# Power.net
KiCad netlist of a schematic drawn in Altium Designer
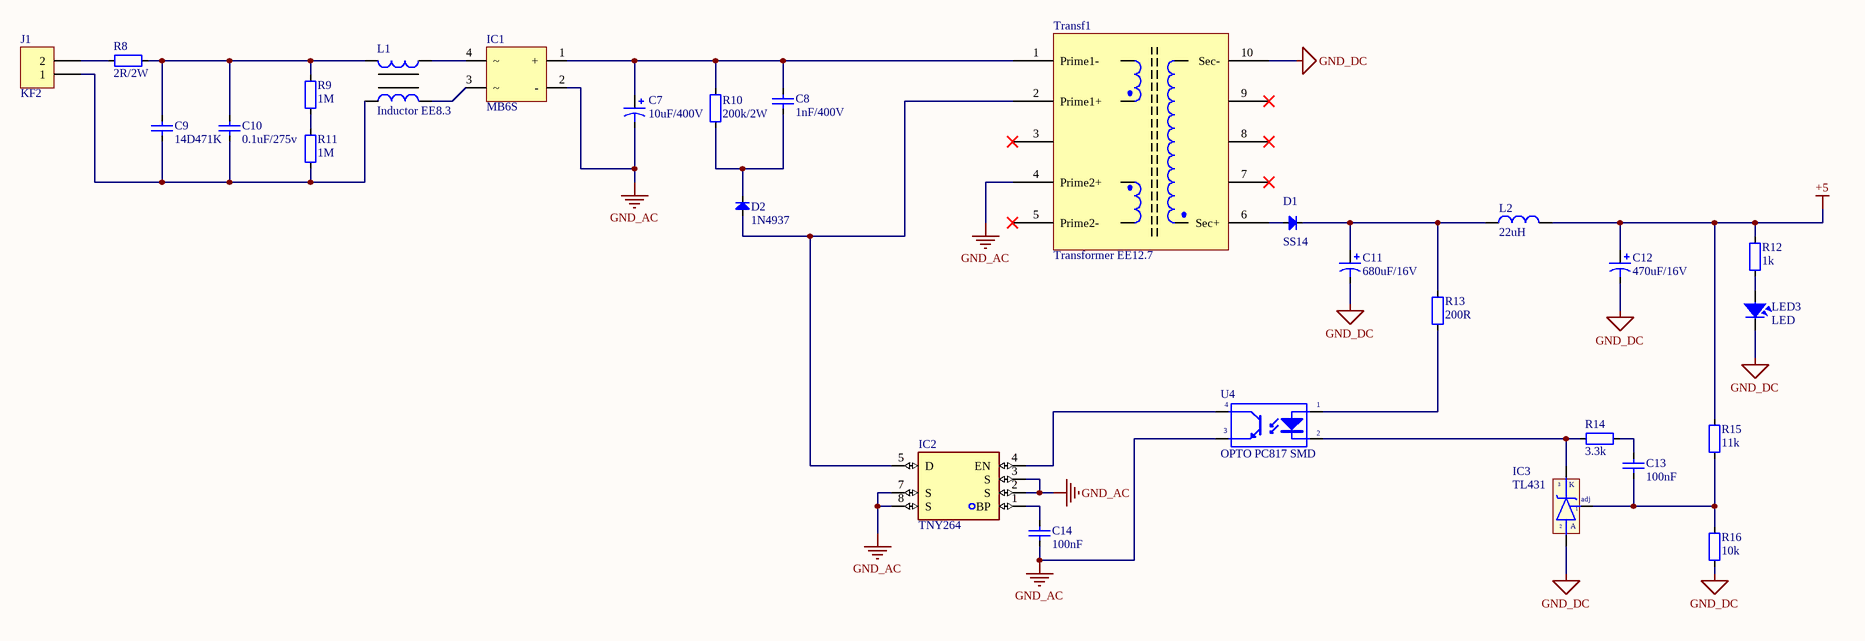
[diagram p0: Power.SchDoc]

(export (version "E")
  (design (tool "Eeschema 10.0.6"))
  (components
    (comp (ref "C7")
      (value "10uF/400V")
      (footprint "C10mm")
      (description "Polarized Capacitor (Axial)")
      (fields (field (name "PUBLISHER") "Altium Limited"))
      (libsource (lib "My Library") (part "Cap Pol"))
    )
    (comp (ref "C8")
      (value "1nF/400V")
      (footprint "103/2KV")
      (description "CAP CERAMIC")
      (fields (field (name "PUBLISHER") "Altium Limited"))
      (libsource (lib "My Library") (part "Cap2KV"))
    )
    (comp (ref "C9")
      (value "14D471K")
      (footprint "103/2KV")
      (description "Capacitor Ceramic 2KV")
      (fields (field (name "PUBLISHER") "Altium Limited"))
      (libsource (lib "My Library") (part "Cap2KV"))
    )
    (comp (ref "C10")
      (value "0.1uF/275v")
      (footprint "Cap AC filter")
      (description "Tụ lọc nguồn AC 0.1uf 275v 10mm")
      (libsource (lib "My Library") (part "Cap AC filter"))
    )
    (comp (ref "C11")
      (value "680uF/16V")
      (footprint "C8mm")
      (description "Polarized Capacitor (Axial)")
      (fields (field (name "PUBLISHER") "Altium Limited"))
      (libsource (lib "My Library") (part "Cap Pol"))
    )
    (comp (ref "C12")
      (value "470uF/16V")
      (footprint "C8mm")
      (description "Polarized Capacitor (Axial)")
      (fields (field (name "PUBLISHER") "Altium Limited"))
      (libsource (lib "My Library") (part "Cap Pol"))
    )
    (comp (ref "C13")
      (value "100nF")
      (footprint "CAP_0805")
      (description "Capacitor")
      (fields (field (name "PUBLISHER") "Altium Limited"))
      (libsource (lib "My Library") (part "CapSMD"))
    )
    (comp (ref "C14")
      (value "100nF")
      (footprint "CAP_0805")
      (description "Capacitor")
      (fields (field (name "PUBLISHER") "Altium Limited"))
      (libsource (lib "My Library") (part "CapSMD"))
    )
    (comp (ref "D1")
      (value "SS14")
      (footprint "DO-214AC(SMA)")
      (description "Diode Schottky\r\n1N5819")
      (fields (field (name "PUBLISHER") "Altium Limited"))
      (libsource (lib "My Library") (part "Diode SMD"))
    )
    (comp (ref "D2")
      (value "1N4937")
      (footprint "DIO-1AN")
      (description "Diode Schottky\r\n1N4937")
      (fields (field (name "PUBLISHER") "Altium Limited"))
      (libsource (lib "My Library") (part "Diode SMD"))
    )
    (comp (ref "IC1") (value "MB6S") (footprint "MB6S") (libsource (lib "My Library") (part "MB6S")))
    (comp (ref "IC2")
      (value "TNY264")
      (footprint "TNY264")
      (description "IC Power")
      (libsource (lib "My Library") (part "TNY264"))
    )
    (comp (ref "IC3")
      (value "TL431")
      (footprint "qto-92")
      (description "Programmable Shunt Regulator")
      (libsource (lib "My Library") (part "TL431"))
    )
    (comp (ref "J1")
      (value "KF2")
      (footprint "KF2-5.08T")
      (fields
        (field (name "MANUFACTURER") "Würth Elektronik eiSos GmbH")
        (field (name "PARTNO") "691103110002")
        (field (name "CREATED BY") "Karrer Zheng")
      )
      (libsource (lib "My Library") (part "KF2"))
    )
    (comp (ref "L1")
      (value "Inductor EE8.3")
      (footprint "Inductor EE8.3")
      (libsource (lib "My Library") (part "Inductor EE8.3"))
    )
    (comp (ref "L2")
      (value "22uH")
      (footprint "L_SMD")
      (description "CD73R 22uH 1.23A 7345")
      (libsource (lib "My Library") (part "Inductor"))
    )
    (comp (ref "LED3")
      (value "LED")
      (footprint "LED-0805-Red")
      (description "LED Single colour Green and Red")
      (libsource (lib "My Library") (part "LED"))
    )
    (comp (ref "R8")
      (value "2R/2W")
      (footprint "RES-1WW")
      (description "Resistor")
      (fields
        (field (name "MANUFACTURER") "Generic Components")
        (field (name "PUBLISHER") "Altium Hobart Technology Centre")
      )
      (libsource (lib "My Library") (part "Resistor - SMD"))
    )
    (comp (ref "R9")
      (value "1M")
      (footprint "RES-SMD-1206")
      (description "Resistor")
      (fields
        (field (name "MANUFACTURER") "Generic Components")
        (field (name "PUBLISHER") "Altium Hobart Technology Centre")
      )
      (libsource (lib "My Library") (part "Resistor - SMD"))
    )
    (comp (ref "R10")
      (value "200k/2W")
      (footprint "RES-1WW")
      (description "Resistor")
      (fields
        (field (name "MANUFACTURER") "Generic Components")
        (field (name "PUBLISHER") "Altium Hobart Technology Centre")
      )
      (libsource (lib "My Library") (part "Resistor - SMD"))
    )
    (comp (ref "R11")
      (value "1M")
      (footprint "RES-SMD-1206")
      (description "Resistor")
      (fields
        (field (name "MANUFACTURER") "Generic Components")
        (field (name "PUBLISHER") "Altium Hobart Technology Centre")
      )
      (libsource (lib "My Library") (part "Resistor - SMD"))
    )
    (comp (ref "R12")
      (value "1k")
      (footprint "RES-SMD-0805")
      (description "Resistor")
      (fields
        (field (name "MANUFACTURER") "Generic Components")
        (field (name "PUBLISHER") "Altium Hobart Technology Centre")
      )
      (libsource (lib "My Library") (part "Resistor - SMD"))
    )
    (comp (ref "R13")
      (value "200R")
      (footprint "RES-SMD-0805")
      (description "Resistor")
      (fields
        (field (name "MANUFACTURER") "Generic Components")
        (field (name "PUBLISHER") "Altium Hobart Technology Centre")
      )
      (libsource (lib "My Library") (part "Resistor - SMD"))
    )
    (comp (ref "R14")
      (value "3.3k")
      (footprint "RES-SMD-0805")
      (description "Resistor")
      (fields
        (field (name "MANUFACTURER") "Generic Components")
        (field (name "PUBLISHER") "Altium Hobart Technology Centre")
      )
      (libsource (lib "My Library") (part "Resistor - SMD"))
    )
    (comp (ref "R15")
      (value "11k")
      (footprint "RES-SMD-0805")
      (description "Resistor")
      (fields
        (field (name "MANUFACTURER") "Generic Components")
        (field (name "PUBLISHER") "Altium Hobart Technology Centre")
      )
      (libsource (lib "My Library") (part "Resistor - SMD"))
    )
    (comp (ref "R16")
      (value "10k")
      (footprint "RES-SMD-0805")
      (description "Resistor")
      (fields
        (field (name "MANUFACTURER") "Generic Components")
        (field (name "PUBLISHER") "Altium Hobart Technology Centre")
      )
      (libsource (lib "My Library") (part "Resistor - SMD"))
    )
    (comp (ref "Transf1")
      (value "Transformer EE12.7")
      (footprint "Transformer EE12.7")
      (libsource (lib "My Library") (part "Tranformer EE16"))
    )
    (comp (ref "U4")
      (value "OPTO PC817 SMD")
      (footprint "SOP4")
      (description "Single Opto")
      (libsource (lib "Altium_Lib_by_KhueNguyenCreator") (part "OPTO PC817 SMD"))
    )
  )
  (nets
    (net (code "1") (name "+5") (class "Default")
      (node (ref "C12") (pin "1") (pinfunction "1_1") (pintype "passive"))
      (node (ref "L2") (pin "2") (pinfunction "2_2") (pintype "passive"))
      (node (ref "R12") (pin "2") (pinfunction "2_2") (pintype "passive"))
      (node (ref "R15") (pin "2") (pinfunction "2_2") (pintype "passive"))
    )
    (net (code "2") (name "GND_AC") (class "Default")
      (node (ref "C14") (pin "1") (pinfunction "1_1") (pintype "passive"))
      (node (ref "C7") (pin "2") (pinfunction "2_2") (pintype "passive"))
      (node (ref "IC1") (pin "2") (pinfunction "-_2") (pintype "passive"))
      (node (ref "IC2") (pin "2") (pinfunction "S_2") (pintype "bidirectional"))
      (node (ref "IC2") (pin "3") (pinfunction "S_3") (pintype "bidirectional"))
      (node (ref "IC2") (pin "7") (pinfunction "S_7") (pintype "bidirectional"))
      (node (ref "IC2") (pin "8") (pinfunction "S_8") (pintype "bidirectional"))
      (node (ref "Transf1") (pin "4") (pinfunction "Prime2+_4") (pintype "passive"))
      (node (ref "U4") (pin "3") (pinfunction "E_3") (pintype "passive"))
    )
    (net (code "3") (name "GND_DC") (class "Default")
      (node (ref "C11") (pin "2") (pinfunction "2_2") (pintype "passive"))
      (node (ref "C12") (pin "2") (pinfunction "2_2") (pintype "passive"))
      (node (ref "IC3") (pin "2") (pinfunction "A_2") (pintype "passive"))
      (node (ref "LED3") (pin "2") (pinfunction "2_2") (pintype "passive"))
      (node (ref "R16") (pin "1") (pinfunction "1_1") (pintype "passive"))
      (node (ref "Transf1") (pin "10") (pinfunction "Sec-_10") (pintype "passive"))
    )
    (net (code "4") (name "Net-(C10-Pad1)") (class "Default")
      (node (ref "C10") (pin "1") (pinfunction "1_1") (pintype "passive"))
      (node (ref "C9") (pin "1") (pinfunction "1_1") (pintype "passive"))
      (node (ref "J1") (pin "1") (pinfunction "1_1") (pintype "passive"))
      (node (ref "L1") (pin "4") (pinfunction "4_4") (pintype "passive"))
      (node (ref "R11") (pin "1") (pinfunction "1_1") (pintype "passive"))
    )
    (net (code "5") (name "Net-(C10-Pad2)") (class "Default")
      (node (ref "C10") (pin "2") (pinfunction "2_2") (pintype "passive"))
      (node (ref "C9") (pin "2") (pinfunction "2_2") (pintype "passive"))
      (node (ref "L1") (pin "2") (pinfunction "2_2") (pintype "passive"))
      (node (ref "R8") (pin "2") (pinfunction "2_2") (pintype "passive"))
      (node (ref "R9") (pin "2") (pinfunction "2_2") (pintype "passive"))
    )
    (net (code "6") (name "Net-(C13-Pad2)") (class "Default")
      (node (ref "C13") (pin "2") (pinfunction "2_2") (pintype "passive"))
      (node (ref "R14") (pin "1") (pinfunction "1_1") (pintype "passive"))
    )
    (net (code "7") (name "Net-(D1-A)") (class "Default")
      (node (ref "D1") (pin "1") (pinfunction "A_1") (pintype "passive"))
      (node (ref "Transf1") (pin "6") (pinfunction "Sec+_6") (pintype "passive"))
    )
    (net (code "8") (name "Net-(D1-K)") (class "Default")
      (node (ref "C11") (pin "1") (pinfunction "1_1") (pintype "passive"))
      (node (ref "D1") (pin "2") (pinfunction "K_2") (pintype "passive"))
      (node (ref "L2") (pin "1") (pinfunction "1_1") (pintype "passive"))
      (node (ref "R13") (pin "2") (pinfunction "2_2") (pintype "passive"))
    )
    (net (code "9") (name "Net-(D2-A)") (class "Default")
      (node (ref "D2") (pin "1") (pinfunction "A_1") (pintype "passive"))
      (node (ref "IC2") (pin "5") (pinfunction "D_5") (pintype "bidirectional"))
      (node (ref "Transf1") (pin "2") (pinfunction "Prime1+_2") (pintype "passive"))
    )
    (net (code "10") (name "Net-(D2-K)") (class "Default")
      (node (ref "C8") (pin "2") (pinfunction "2_2") (pintype "passive"))
      (node (ref "D2") (pin "2") (pinfunction "K_2") (pintype "passive"))
      (node (ref "R10") (pin "1") (pinfunction "1_1") (pintype "passive"))
    )
    (net (code "11") (name "Net-(IC1-+)") (class "Default")
      (node (ref "C7") (pin "1") (pinfunction "1_1") (pintype "passive"))
      (node (ref "C8") (pin "1") (pinfunction "1_1") (pintype "passive"))
      (node (ref "IC1") (pin "1") (pinfunction "+_1") (pintype "passive"))
      (node (ref "R10") (pin "2") (pinfunction "2_2") (pintype "passive"))
      (node (ref "Transf1") (pin "1") (pinfunction "Prime1-_1") (pintype "passive"))
    )
    (net (code "12") (name "Net-(IC1-~-Pad3)") (class "Default")
      (node (ref "IC1") (pin "3") (pinfunction "~_3") (pintype "passive"))
      (node (ref "L1") (pin "3") (pinfunction "3_3") (pintype "passive"))
    )
    (net (code "13") (name "Net-(IC1-~-Pad4)") (class "Default")
      (node (ref "IC1") (pin "4") (pinfunction "~_4") (pintype "passive"))
      (node (ref "L1") (pin "1") (pinfunction "1_1") (pintype "passive"))
    )
    (net (code "14") (name "Net-(IC2-BP)") (class "Default")
      (node (ref "C14") (pin "2") (pinfunction "2_2") (pintype "passive"))
      (node (ref "IC2") (pin "1") (pinfunction "BP_1") (pintype "bidirectional"))
    )
    (net (code "15") (name "Net-(IC2-EN)") (class "Default")
      (node (ref "IC2") (pin "4") (pinfunction "EN_4") (pintype "bidirectional"))
      (node (ref "U4") (pin "4") (pinfunction "C_4") (pintype "passive"))
    )
    (net (code "16") (name "Net-(IC3-K)") (class "Default")
      (node (ref "IC3") (pin "3") (pinfunction "K_3") (pintype "passive"))
      (node (ref "R14") (pin "2") (pinfunction "2_2") (pintype "passive"))
      (node (ref "U4") (pin "2") (pinfunction "K_2") (pintype "passive"))
    )
    (net (code "17") (name "Net-(IC3-adj)") (class "Default")
      (node (ref "C13") (pin "1") (pinfunction "1_1") (pintype "passive"))
      (node (ref "IC3") (pin "1") (pinfunction "adj_1") (pintype "passive"))
      (node (ref "R15") (pin "1") (pinfunction "1_1") (pintype "passive"))
      (node (ref "R16") (pin "2") (pinfunction "2_2") (pintype "passive"))
    )
    (net (code "18") (name "Net-(J1-Pad2)") (class "Default")
      (node (ref "J1") (pin "2") (pinfunction "2_2") (pintype "passive"))
      (node (ref "R8") (pin "1") (pinfunction "1_1") (pintype "passive"))
    )
    (net (code "19") (name "Net-(LED3-Pad1)") (class "Default")
      (node (ref "LED3") (pin "1") (pinfunction "1_1") (pintype "passive"))
      (node (ref "R12") (pin "1") (pinfunction "1_1") (pintype "passive"))
    )
    (net (code "20") (name "Net-(R11-Pad2)") (class "Default")
      (node (ref "R11") (pin "2") (pinfunction "2_2") (pintype "passive"))
      (node (ref "R9") (pin "1") (pinfunction "1_1") (pintype "passive"))
    )
    (net (code "21") (name "Net-(U4-A)") (class "Default")
      (node (ref "R13") (pin "1") (pinfunction "1_1") (pintype "passive"))
      (node (ref "U4") (pin "1") (pinfunction "A_1") (pintype "passive"))
    )
    (net (code "22") (name "unconnected-(Transf1-Pad3)") (class "Default")
      (node (ref "Transf1") (pin "3") (pintype "passive+no_connect"))
    )
    (net (code "23") (name "unconnected-(Transf1-Pad7)") (class "Default")
      (node (ref "Transf1") (pin "7") (pintype "passive+no_connect"))
    )
    (net (code "24") (name "unconnected-(Transf1-Pad8)") (class "Default")
      (node (ref "Transf1") (pin "8") (pintype "passive+no_connect"))
    )
    (net (code "25") (name "unconnected-(Transf1-Pad9)") (class "Default")
      (node (ref "Transf1") (pin "9") (pintype "passive+no_connect"))
    )
    (net (code "26") (name "unconnected-(Transf1-Prime2--Pad5)") (class "Default")
      (node (ref "Transf1") (pin "5") (pinfunction "Prime2-_5") (pintype "passive+no_connect"))
    )
  )
)
